# mcu.net
KiCad netlist of a schematic drawn in Altium Designer
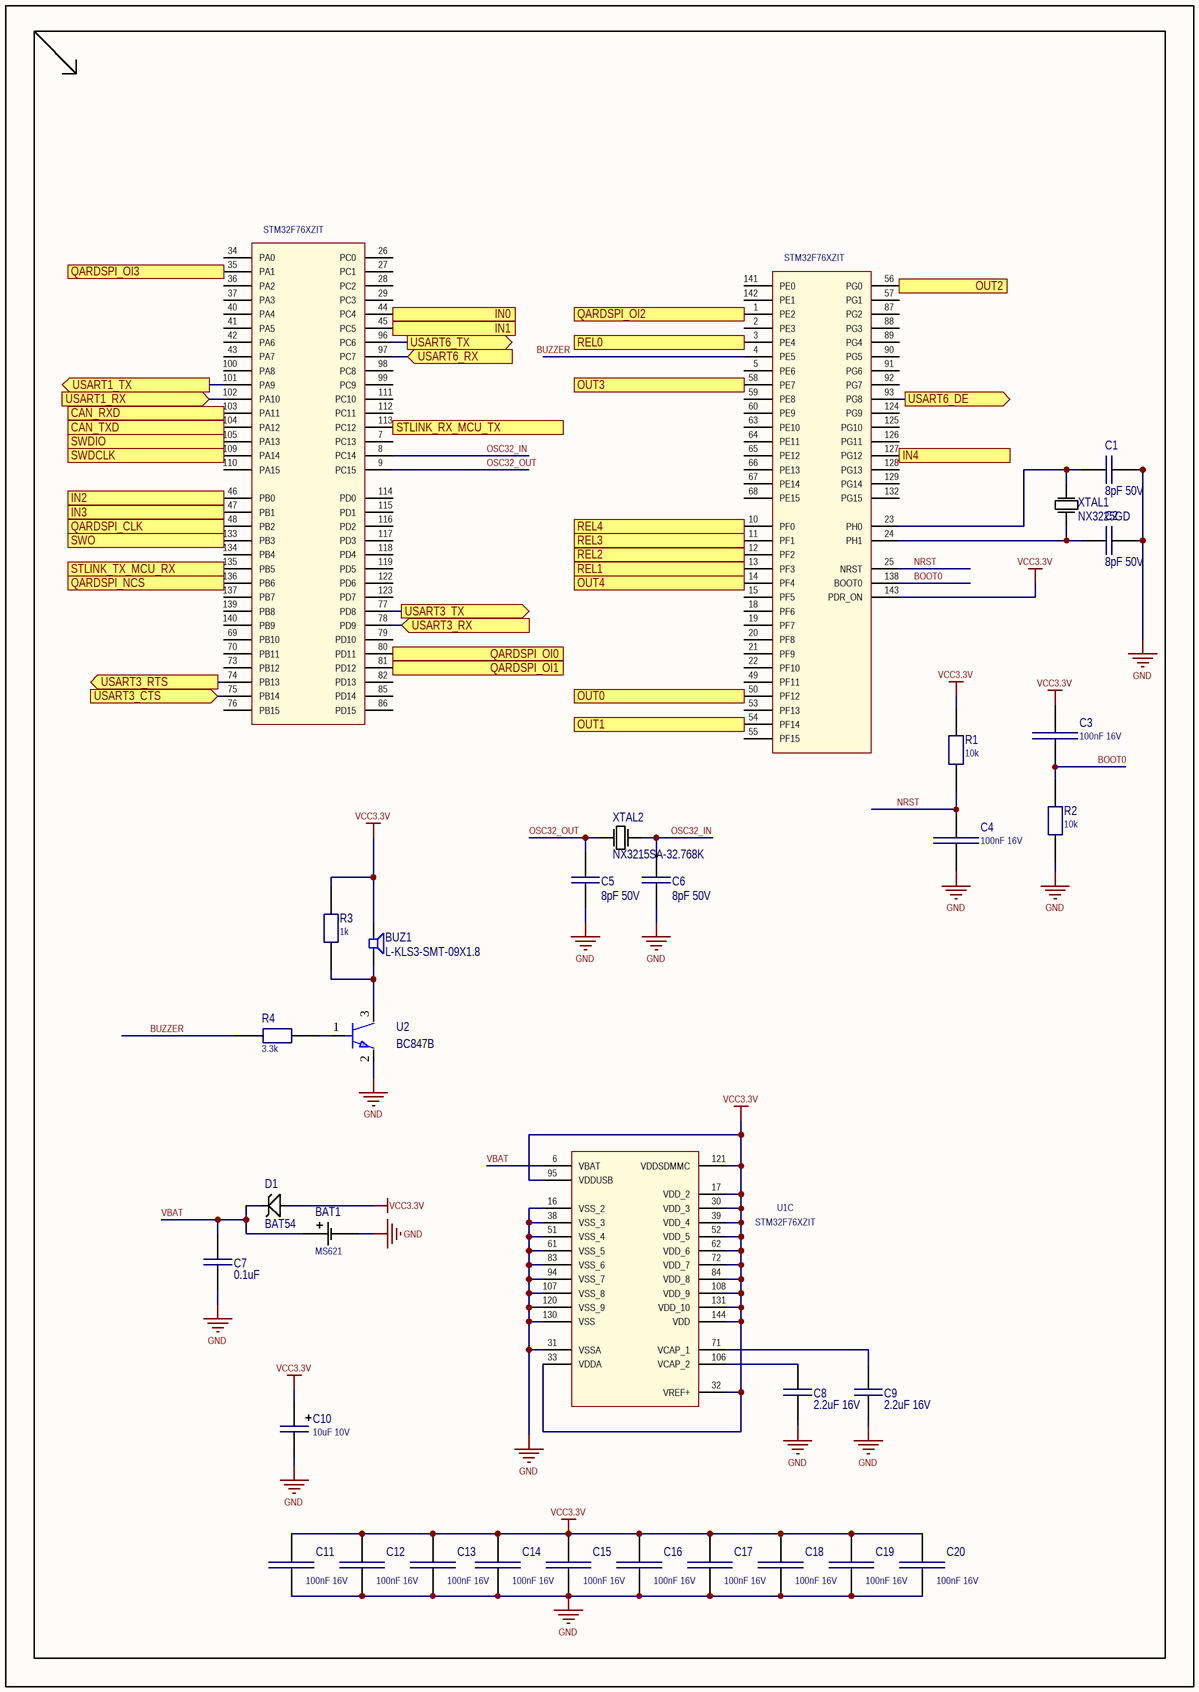
[diagram p0: mcu.schdoc]

(export (version "E")
  (design (tool "Eeschema 10.0.6"))
  (components
    (comp (ref "BAT1")
      (value "MS621")
      (footprint "battery_socets:MS621")
      (description "Battery")
      (libsource (lib "battery_socets") (part "MS621"))
    )
    (comp (ref "BUZ1")
      (value "L-KLS3-SMT-09X1.8")
      (footprint "SPKR_PKMCS0909E4000-R1")
      (description "Piezoelectric Sounders")
      (fields (field (name "ALTERNATIVE PART") "PKLCS1212E40A1-R1"))
      (libsource (lib "other") (part "BUZZER"))
    )
    (comp (ref "C1")
      (value "8pF 50V")
      (footprint "C_0603")
      (description "Capacitor")
      (fields (field (name "PART NUMBER") "CC0603DRNPO9BN8R0"))
      (libsource (lib "capacitors") (part "CAP_SMD"))
    )
    (comp (ref "C2")
      (value "8pF 50V")
      (footprint "C_0603")
      (description "Capacitor")
      (fields (field (name "PART NUMBER") "CC0603DRNPO9BN8R0"))
      (libsource (lib "capacitors") (part "CAP_SMD"))
    )
    (comp (ref "C3")
      (value "100nF 16V")
      (footprint "C_0603")
      (description "Capacitor")
      (fields (field (name "PART NUMBER") "CC0603KPX7R9BB104"))
      (libsource (lib "AX_Altium_v2.3") (part "C0603"))
    )
    (comp (ref "C4")
      (value "100nF 16V")
      (footprint "C_0603")
      (description "Capacitor")
      (fields (field (name "PART NUMBER") "CC0603KPX7R9BB104"))
      (libsource (lib "AX_Altium_v2.3") (part "C0603"))
    )
    (comp (ref "C5")
      (value "8pF 50V")
      (footprint "C_0603")
      (description "Capacitor")
      (fields (field (name "PART NUMBER") "CC0603DRNPO9BN8R0"))
      (libsource (lib "capacitors") (part "CAP_SMD"))
    )
    (comp (ref "C6")
      (value "8pF 50V")
      (footprint "C_0603")
      (description "Capacitor")
      (fields (field (name "PART NUMBER") "CC0603DRNPO9BN8R0"))
      (libsource (lib "capacitors") (part "CAP_SMD"))
    )
    (comp (ref "C7")
      (value "0.1uF")
      (footprint "C_0603")
      (description "Capacitor")
      (fields (field (name "PART NUMBER") "CC0603KPX7R9BB104"))
      (libsource (lib "capacitors") (part "CAP_SMD"))
    )
    (comp (ref "C8")
      (value "2.2uF 16V")
      (footprint "C_0603")
      (description "Capacitor")
      (fields (field (name "PART NUMBER") "CC0603KRX5R7BB225"))
      (libsource (lib "capacitors") (part "CAP_SMD"))
    )
    (comp (ref "C9")
      (value "2.2uF 16V")
      (footprint "C_0603")
      (description "Capacitor")
      (fields (field (name "PART NUMBER") "CC0603KRX5R7BB225"))
      (libsource (lib "capacitors") (part "CAP_SMD"))
    )
    (comp (ref "C10")
      (value "10uF 10V")
      (footprint "TANTAL_TYPE_A")
      (description "Tantal Capacitor")
      (fields (field (name "PART NUMBER") "293D106X9010A2TE3"))
      (libsource (lib "capacitors") (part "TANTAL_CAP"))
    )
    (comp (ref "C11")
      (value "100nF 16V")
      (footprint "C_0603")
      (description "Capacitor")
      (fields (field (name "PART NUMBER") "CC0603KPX7R9BB104"))
      (libsource (lib "AX_Altium_v2.3") (part "C0603"))
    )
    (comp (ref "C12")
      (value "100nF 16V")
      (footprint "C_0603")
      (description "Capacitor")
      (fields (field (name "PART NUMBER") "CC0603KPX7R9BB104"))
      (libsource (lib "AX_Altium_v2.3") (part "C0603"))
    )
    (comp (ref "C13")
      (value "100nF 16V")
      (footprint "C_0603")
      (description "Capacitor")
      (fields (field (name "PART NUMBER") "CC0603KPX7R9BB104"))
      (libsource (lib "AX_Altium_v2.3") (part "C0603"))
    )
    (comp (ref "C14")
      (value "100nF 16V")
      (footprint "C_0603")
      (description "Capacitor")
      (fields (field (name "PART NUMBER") "CC0603KPX7R9BB104"))
      (libsource (lib "AX_Altium_v2.3") (part "C0603"))
    )
    (comp (ref "C15")
      (value "100nF 16V")
      (footprint "C_0603")
      (description "Capacitor")
      (fields (field (name "PART NUMBER") "CC0603KPX7R9BB104"))
      (libsource (lib "AX_Altium_v2.3") (part "C0603"))
    )
    (comp (ref "C16")
      (value "100nF 16V")
      (footprint "C_0603")
      (description "Capacitor")
      (fields (field (name "PART NUMBER") "CC0603KPX7R9BB104"))
      (libsource (lib "AX_Altium_v2.3") (part "C0603"))
    )
    (comp (ref "C17")
      (value "100nF 16V")
      (footprint "C_0603")
      (description "Capacitor")
      (fields (field (name "PART NUMBER") "CC0603KPX7R9BB104"))
      (libsource (lib "AX_Altium_v2.3") (part "C0603"))
    )
    (comp (ref "C18")
      (value "100nF 16V")
      (footprint "C_0603")
      (description "Capacitor")
      (fields (field (name "PART NUMBER") "CC0603KPX7R9BB104"))
      (libsource (lib "AX_Altium_v2.3") (part "C0603"))
    )
    (comp (ref "C19")
      (value "100nF 16V")
      (footprint "C_0603")
      (description "Capacitor")
      (fields (field (name "PART NUMBER") "CC0603KPX7R9BB104"))
      (libsource (lib "AX_Altium_v2.3") (part "C0603"))
    )
    (comp (ref "C20")
      (value "100nF 16V")
      (footprint "C_0603")
      (description "Capacitor")
      (fields (field (name "PART NUMBER") "CC0603KPX7R9BB104"))
      (libsource (lib "AX_Altium_v2.3") (part "C0603"))
    )
    (comp (ref "D1")
      (value "BAT54")
      (footprint "SOT23")
      (description "Diode")
      (libsource (lib "diode") (part "BAT54"))
    )
    (comp (ref "R1")
      (value "10k")
      (footprint "R_0603")
      (description "Resistor")
      (fields (field (name "PART NUMBER") "RC0603FR-0710KL"))
      (libsource (lib "resistors") (part "RES_SMD"))
    )
    (comp (ref "R2")
      (value "10k")
      (footprint "R_0603")
      (description "Resistor")
      (fields (field (name "PART NUMBER") "RC0603FR-0710KL"))
      (libsource (lib "resistors") (part "RES_SMD"))
    )
    (comp (ref "R3")
      (value "1k")
      (footprint "R_0603")
      (description "Resistor")
      (fields (field (name "PART NUMBER") "RC0603FR-071KL"))
      (libsource (lib "resistors") (part "RES_SMD"))
    )
    (comp (ref "R4")
      (value "3.3k")
      (footprint "R_0603")
      (description "Resistor")
      (fields (field (name "PART NUMBER") "RC0603FR-073K3L"))
      (libsource (lib "resistors") (part "RES_SMD"))
    )
    (comp (ref "U1")
      (value "STM32F76XZIT")
      (footprint "TQFP144_M")
      (description "MCU")
      (fields
        (field (name "MANUFACTURER_PART_NUMBER") "STM32F76XZXT")
        (field (name "PART NUMBER") "STM32F765ZGT")
        (field (name "COPYRIGHT") "Copyright (C) 2016 Accelerated Designs. All rights reserved")
      )
      (libsource (lib "STM32 F4") (part "STM32F76XZXT"))
    )
    (comp (ref "U2")
      (value "BC847B")
      (footprint "SOT23")
      (description "Transistor")
      (libsource (lib "AX_Altium_v2.3") (part "BC847B"))
    )
    (comp (ref "XTAL1")
      (value "NX3225GD")
      (footprint "NX3225GD")
      (description "Crystal Oscillator")
      (fields (field (name "PART NUMBER") "NX3225GD-8MHZ-EXS00A-CG05041"))
      (libsource (lib "crystals_oscillators") (part "NX3225GD"))
    )
    (comp (ref "XTAL2")
      (value "NX3215SA-32.768K")
      (footprint "XTAL_NX3215SA-32.768K-STD-MUA-8")
      (description "Crystal Oscillator")
      (fields (field (name "PART NUMBER") "NX3215SA-32.768K-10PPM-45KOHM-6PF"))
      (libsource (lib "crystals_oscillators") (part "NX3215SA-32.768K"))
    )
  )
  (nets
    (net (code "1") (name "/BOOT0") (class "Default")
      (node (ref "C3") (pin "2") (pinfunction "2_2") (pintype "passive"))
      (node (ref "R2") (pin "2") (pinfunction "2_2") (pintype "passive"))
      (node (ref "U1") (pin "138") (pinfunction "BOOT0_138") (pintype "passive"))
    )
    (net (code "2") (name "/BUZZER") (class "Default")
      (node (ref "R4") (pin "1") (pinfunction "1_1") (pintype "passive"))
      (node (ref "U1") (pin "4") (pinfunction "PE5_4") (pintype "passive"))
    )
    (net (code "3") (name "/CAN_RXD") (class "Default")
      (node (ref "U1") (pin "103") (pinfunction "PA11_103") (pintype "passive"))
    )
    (net (code "4") (name "/CAN_TXD") (class "Default")
      (node (ref "U1") (pin "104") (pinfunction "PA12_104") (pintype "passive"))
    )
    (net (code "5") (name "/IN0") (class "Default")
      (node (ref "U1") (pin "44") (pinfunction "PC4_44") (pintype "passive"))
    )
    (net (code "6") (name "/IN1") (class "Default")
      (node (ref "U1") (pin "45") (pinfunction "PC5_45") (pintype "passive"))
    )
    (net (code "7") (name "/IN2") (class "Default")
      (node (ref "U1") (pin "46") (pinfunction "PB0_46") (pintype "passive"))
    )
    (net (code "8") (name "/IN3") (class "Default")
      (node (ref "U1") (pin "47") (pinfunction "PB1_47") (pintype "passive"))
    )
    (net (code "9") (name "/IN4") (class "Default")
      (node (ref "U1") (pin "127") (pinfunction "PG12_127") (pintype "passive"))
    )
    (net (code "10") (name "/NRST") (class "Default")
      (node (ref "C4") (pin "2") (pinfunction "2_2") (pintype "passive"))
      (node (ref "R1") (pin "1") (pinfunction "1_1") (pintype "passive"))
      (node (ref "U1") (pin "25") (pinfunction "NRST_25") (pintype "passive"))
    )
    (net (code "11") (name "/OSC32_IN") (class "Default")
      (node (ref "C6") (pin "2") (pinfunction "2_2") (pintype "passive"))
      (node (ref "U1") (pin "8") (pinfunction "PC14_8") (pintype "passive"))
      (node (ref "XTAL2") (pin "2") (pinfunction "OSC2_2") (pintype "passive"))
    )
    (net (code "12") (name "/OSC32_OUT") (class "Default")
      (node (ref "C5") (pin "2") (pinfunction "2_2") (pintype "passive"))
      (node (ref "U1") (pin "9") (pinfunction "PC15_9") (pintype "passive"))
      (node (ref "XTAL2") (pin "1") (pinfunction "OSC1_1") (pintype "passive"))
    )
    (net (code "13") (name "/OUT0") (class "Default")
      (node (ref "U1") (pin "50") (pinfunction "PF12_50") (pintype "passive"))
    )
    (net (code "14") (name "/OUT1") (class "Default")
      (node (ref "U1") (pin "54") (pinfunction "PF14_54") (pintype "passive"))
    )
    (net (code "15") (name "/OUT2") (class "Default")
      (node (ref "U1") (pin "56") (pinfunction "PG0_56") (pintype "passive"))
    )
    (net (code "16") (name "/OUT3") (class "Default")
      (node (ref "U1") (pin "58") (pinfunction "PE7_58") (pintype "passive"))
    )
    (net (code "17") (name "/OUT4") (class "Default")
      (node (ref "U1") (pin "14") (pinfunction "PF4_14") (pintype "passive"))
    )
    (net (code "18") (name "/QARDSPI_CLK") (class "Default")
      (node (ref "U1") (pin "48") (pinfunction "PB2_48") (pintype "passive"))
    )
    (net (code "19") (name "/QARDSPI_NCS") (class "Default")
      (node (ref "U1") (pin "136") (pinfunction "PB6_136") (pintype "passive"))
    )
    (net (code "20") (name "/QARDSPI_OI0") (class "Default")
      (node (ref "U1") (pin "80") (pinfunction "PD11_80") (pintype "passive"))
    )
    (net (code "21") (name "/QARDSPI_OI1") (class "Default")
      (node (ref "U1") (pin "81") (pinfunction "PD12_81") (pintype "passive"))
    )
    (net (code "22") (name "/QARDSPI_OI2") (class "Default")
      (node (ref "U1") (pin "1") (pinfunction "PE2_1") (pintype "passive"))
    )
    (net (code "23") (name "/QARDSPI_OI3") (class "Default")
      (node (ref "U1") (pin "35") (pinfunction "PA1_35") (pintype "passive"))
    )
    (net (code "24") (name "/REL0") (class "Default")
      (node (ref "U1") (pin "3") (pinfunction "PE4_3") (pintype "passive"))
    )
    (net (code "25") (name "/REL1") (class "Default")
      (node (ref "U1") (pin "13") (pinfunction "PF3_13") (pintype "passive"))
    )
    (net (code "26") (name "/REL2") (class "Default")
      (node (ref "U1") (pin "12") (pinfunction "PF2_12") (pintype "passive"))
    )
    (net (code "27") (name "/REL3") (class "Default")
      (node (ref "U1") (pin "11") (pinfunction "PF1_11") (pintype "passive"))
    )
    (net (code "28") (name "/REL4") (class "Default")
      (node (ref "U1") (pin "10") (pinfunction "PF0_10") (pintype "passive"))
    )
    (net (code "29") (name "/STLINK_RX_MCU_TX") (class "Default")
      (node (ref "U1") (pin "113") (pinfunction "PC12_113") (pintype "passive"))
    )
    (net (code "30") (name "/STLINK_TX_MCU_RX") (class "Default")
      (node (ref "U1") (pin "135") (pinfunction "PB5_135") (pintype "passive"))
    )
    (net (code "31") (name "/SWDCLK") (class "Default")
      (node (ref "U1") (pin "109") (pinfunction "PA14_109") (pintype "passive"))
    )
    (net (code "32") (name "/SWDIO") (class "Default")
      (node (ref "U1") (pin "105") (pinfunction "PA13_105") (pintype "passive"))
    )
    (net (code "33") (name "/SWO") (class "Default")
      (node (ref "U1") (pin "133") (pinfunction "PB3_133") (pintype "passive"))
    )
    (net (code "34") (name "/USART1_RX") (class "Default")
      (node (ref "U1") (pin "102") (pinfunction "PA10_102") (pintype "passive"))
    )
    (net (code "35") (name "/USART1_TX") (class "Default")
      (node (ref "U1") (pin "101") (pinfunction "PA9_101") (pintype "passive"))
    )
    (net (code "36") (name "/USART3_CTS") (class "Default")
      (node (ref "U1") (pin "75") (pinfunction "PB14_75") (pintype "passive"))
    )
    (net (code "37") (name "/USART3_RTS") (class "Default")
      (node (ref "U1") (pin "74") (pinfunction "PB13_74") (pintype "passive"))
    )
    (net (code "38") (name "/USART3_RX") (class "Default")
      (node (ref "U1") (pin "78") (pinfunction "PD9_78") (pintype "passive"))
    )
    (net (code "39") (name "/USART3_TX") (class "Default")
      (node (ref "U1") (pin "77") (pinfunction "PD8_77") (pintype "passive"))
    )
    (net (code "40") (name "/USART6_DE") (class "Default")
      (node (ref "U1") (pin "93") (pinfunction "PG8_93") (pintype "passive"))
    )
    (net (code "41") (name "/USART6_RX") (class "Default")
      (node (ref "U1") (pin "97") (pinfunction "PC7_97") (pintype "passive"))
    )
    (net (code "42") (name "/USART6_TX") (class "Default")
      (node (ref "U1") (pin "96") (pinfunction "PC6_96") (pintype "passive"))
    )
    (net (code "43") (name "/VBAT") (class "Default")
      (node (ref "BAT1") (pin "1") (pinfunction "+_1") (pintype "passive"))
      (node (ref "C7") (pin "2") (pinfunction "2_2") (pintype "passive"))
      (node (ref "D1") (pin "3") (pinfunction "3_3") (pintype "passive"))
      (node (ref "U1") (pin "6") (pinfunction "VBAT_6") (pintype "passive"))
    )
    (net (code "44") (name "GND") (class "Default")
      (node (ref "BAT1") (pin "0") (pinfunction "-_0") (pintype "passive"))
      (node (ref "C1") (pin "1") (pinfunction "1_1") (pintype "passive"))
      (node (ref "C10") (pin "2") (pinfunction "2_2") (pintype "passive"))
      (node (ref "C11") (pin "1") (pinfunction "1_1") (pintype "passive"))
      (node (ref "C12") (pin "1") (pinfunction "1_1") (pintype "passive"))
      (node (ref "C13") (pin "1") (pinfunction "1_1") (pintype "passive"))
      (node (ref "C14") (pin "1") (pinfunction "1_1") (pintype "passive"))
      (node (ref "C15") (pin "1") (pinfunction "1_1") (pintype "passive"))
      (node (ref "C16") (pin "1") (pinfunction "1_1") (pintype "passive"))
      (node (ref "C17") (pin "1") (pinfunction "1_1") (pintype "passive"))
      (node (ref "C18") (pin "1") (pinfunction "1_1") (pintype "passive"))
      (node (ref "C19") (pin "1") (pinfunction "1_1") (pintype "passive"))
      (node (ref "C2") (pin "1") (pinfunction "1_1") (pintype "passive"))
      (node (ref "C20") (pin "1") (pinfunction "1_1") (pintype "passive"))
      (node (ref "C4") (pin "1") (pinfunction "1_1") (pintype "passive"))
      (node (ref "C5") (pin "1") (pinfunction "1_1") (pintype "passive"))
      (node (ref "C6") (pin "1") (pinfunction "1_1") (pintype "passive"))
      (node (ref "C7") (pin "1") (pinfunction "1_1") (pintype "passive"))
      (node (ref "C8") (pin "1") (pinfunction "1_1") (pintype "passive"))
      (node (ref "C9") (pin "1") (pinfunction "1_1") (pintype "passive"))
      (node (ref "R2") (pin "1") (pinfunction "1_1") (pintype "passive"))
      (node (ref "U1") (pin "107") (pinfunction "VSS_8_107") (pintype "passive"))
      (node (ref "U1") (pin "120") (pinfunction "VSS_9_120") (pintype "passive"))
      (node (ref "U1") (pin "130") (pinfunction "VSS_130") (pintype "passive"))
      (node (ref "U1") (pin "16") (pinfunction "VSS_2_16") (pintype "passive"))
      (node (ref "U1") (pin "31") (pinfunction "VSSA_31") (pintype "passive"))
      (node (ref "U1") (pin "38") (pinfunction "VSS_3_38") (pintype "passive"))
      (node (ref "U1") (pin "51") (pinfunction "VSS_4_51") (pintype "passive"))
      (node (ref "U1") (pin "61") (pinfunction "VSS_5_61") (pintype "passive"))
      (node (ref "U1") (pin "83") (pinfunction "VSS_6_83") (pintype "passive"))
      (node (ref "U1") (pin "94") (pinfunction "VSS_7_94") (pintype "passive"))
      (node (ref "U2") (pin "2") (pintype "passive"))
    )
    (net (code "45") (name "Net-(BUZ1-Pad2)") (class "Default")
      (node (ref "BUZ1") (pin "2") (pinfunction "2_2") (pintype "passive"))
      (node (ref "R3") (pin "1") (pinfunction "1_1") (pintype "passive"))
      (node (ref "U2") (pin "3") (pintype "passive"))
    )
    (net (code "46") (name "Net-(R4-Pad2)") (class "Default")
      (node (ref "R4") (pin "2") (pinfunction "2_2") (pintype "passive"))
      (node (ref "U2") (pin "1") (pintype "passive"))
    )
    (net (code "47") (name "Net-(U1B-PH0)") (class "Default")
      (node (ref "C1") (pin "2") (pinfunction "2_2") (pintype "passive"))
      (node (ref "U1") (pin "23") (pinfunction "PH0_23") (pintype "passive"))
      (node (ref "XTAL1") (pin "2") (pinfunction "OSC2_2") (pintype "passive"))
    )
    (net (code "48") (name "Net-(U1B-PH1)") (class "Default")
      (node (ref "C2") (pin "2") (pinfunction "2_2") (pintype "passive"))
      (node (ref "U1") (pin "24") (pinfunction "PH1_24") (pintype "passive"))
      (node (ref "XTAL1") (pin "1") (pinfunction "OSC1_1") (pintype "passive"))
    )
    (net (code "49") (name "Net-(U1C-VCAP_1)") (class "Default")
      (node (ref "C9") (pin "2") (pinfunction "2_2") (pintype "passive"))
      (node (ref "U1") (pin "71") (pinfunction "VCAP_1_71") (pintype "passive"))
    )
    (net (code "50") (name "Net-(U1C-VCAP_2)") (class "Default")
      (node (ref "C8") (pin "2") (pinfunction "2_2") (pintype "passive"))
      (node (ref "U1") (pin "106") (pinfunction "VCAP_2_106") (pintype "passive"))
    )
    (net (code "51") (name "VCC3.3V") (class "Default")
      (node (ref "BUZ1") (pin "1") (pinfunction "1_1") (pintype "passive"))
      (node (ref "C10") (pin "1") (pinfunction "1_1") (pintype "passive"))
      (node (ref "C11") (pin "2") (pinfunction "2_2") (pintype "passive"))
      (node (ref "C12") (pin "2") (pinfunction "2_2") (pintype "passive"))
      (node (ref "C13") (pin "2") (pinfunction "2_2") (pintype "passive"))
      (node (ref "C14") (pin "2") (pinfunction "2_2") (pintype "passive"))
      (node (ref "C15") (pin "2") (pinfunction "2_2") (pintype "passive"))
      (node (ref "C16") (pin "2") (pinfunction "2_2") (pintype "passive"))
      (node (ref "C17") (pin "2") (pinfunction "2_2") (pintype "passive"))
      (node (ref "C18") (pin "2") (pinfunction "2_2") (pintype "passive"))
      (node (ref "C19") (pin "2") (pinfunction "2_2") (pintype "passive"))
      (node (ref "C20") (pin "2") (pinfunction "2_2") (pintype "passive"))
      (node (ref "C3") (pin "1") (pinfunction "1_1") (pintype "passive"))
      (node (ref "D1") (pin "1") (pinfunction "1_1") (pintype "passive"))
      (node (ref "R1") (pin "2") (pinfunction "2_2") (pintype "passive"))
      (node (ref "R3") (pin "2") (pinfunction "2_2") (pintype "passive"))
      (node (ref "U1") (pin "108") (pinfunction "VDD_9_108") (pintype "passive"))
      (node (ref "U1") (pin "121") (pinfunction "VDDSDMMC_121") (pintype "passive"))
      (node (ref "U1") (pin "131") (pinfunction "VDD_10_131") (pintype "passive"))
      (node (ref "U1") (pin "143") (pinfunction "PDR_ON_143") (pintype "passive"))
      (node (ref "U1") (pin "144") (pinfunction "VDD_144") (pintype "passive"))
      (node (ref "U1") (pin "17") (pinfunction "VDD_2_17") (pintype "passive"))
      (node (ref "U1") (pin "30") (pinfunction "VDD_3_30") (pintype "passive"))
      (node (ref "U1") (pin "32") (pinfunction "VREF+_32") (pintype "passive"))
      (node (ref "U1") (pin "33") (pinfunction "VDDA_33") (pintype "passive"))
      (node (ref "U1") (pin "39") (pinfunction "VDD_4_39") (pintype "passive"))
      (node (ref "U1") (pin "52") (pinfunction "VDD_5_52") (pintype "passive"))
      (node (ref "U1") (pin "62") (pinfunction "VDD_6_62") (pintype "passive"))
      (node (ref "U1") (pin "72") (pinfunction "VDD_7_72") (pintype "passive"))
      (node (ref "U1") (pin "84") (pinfunction "VDD_8_84") (pintype "passive"))
      (node (ref "U1") (pin "95") (pinfunction "VDDUSB_95") (pintype "passive"))
    )
    (net (code "52") (name "unconnected-(U1A-PA0-Pad34)") (class "Default")
      (node (ref "U1") (pin "34") (pinfunction "PA0_34") (pintype "passive"))
    )
    (net (code "53") (name "unconnected-(U1A-PA2-Pad36)") (class "Default")
      (node (ref "U1") (pin "36") (pinfunction "PA2_36") (pintype "passive"))
    )
    (net (code "54") (name "unconnected-(U1A-PA3-Pad37)") (class "Default")
      (node (ref "U1") (pin "37") (pinfunction "PA3_37") (pintype "passive"))
    )
    (net (code "55") (name "unconnected-(U1A-PA4-Pad40)") (class "Default")
      (node (ref "U1") (pin "40") (pinfunction "PA4_40") (pintype "passive"))
    )
    (net (code "56") (name "unconnected-(U1A-PA5-Pad41)") (class "Default")
      (node (ref "U1") (pin "41") (pinfunction "PA5_41") (pintype "passive"))
    )
    (net (code "57") (name "unconnected-(U1A-PA6-Pad42)") (class "Default")
      (node (ref "U1") (pin "42") (pinfunction "PA6_42") (pintype "passive"))
    )
    (net (code "58") (name "unconnected-(U1A-PA7-Pad43)") (class "Default")
      (node (ref "U1") (pin "43") (pinfunction "PA7_43") (pintype "passive"))
    )
    (net (code "59") (name "unconnected-(U1A-PA8-Pad100)") (class "Default")
      (node (ref "U1") (pin "100") (pinfunction "PA8_100") (pintype "passive"))
    )
    (net (code "60") (name "unconnected-(U1A-PA15-Pad110)") (class "Default")
      (node (ref "U1") (pin "110") (pinfunction "PA15_110") (pintype "passive"))
    )
    (net (code "61") (name "unconnected-(U1A-PB4-Pad134)") (class "Default")
      (node (ref "U1") (pin "134") (pinfunction "PB4_134") (pintype "passive"))
    )
    (net (code "62") (name "unconnected-(U1A-PB7-Pad137)") (class "Default")
      (node (ref "U1") (pin "137") (pinfunction "PB7_137") (pintype "passive"))
    )
    (net (code "63") (name "unconnected-(U1A-PB8-Pad139)") (class "Default")
      (node (ref "U1") (pin "139") (pinfunction "PB8_139") (pintype "passive"))
    )
    (net (code "64") (name "unconnected-(U1A-PB9-Pad140)") (class "Default")
      (node (ref "U1") (pin "140") (pinfunction "PB9_140") (pintype "passive"))
    )
    (net (code "65") (name "unconnected-(U1A-PB10-Pad69)") (class "Default")
      (node (ref "U1") (pin "69") (pinfunction "PB10_69") (pintype "passive"))
    )
    (net (code "66") (name "unconnected-(U1A-PB11-Pad70)") (class "Default")
      (node (ref "U1") (pin "70") (pinfunction "PB11_70") (pintype "passive"))
    )
    (net (code "67") (name "unconnected-(U1A-PB12-Pad73)") (class "Default")
      (node (ref "U1") (pin "73") (pinfunction "PB12_73") (pintype "passive"))
    )
    (net (code "68") (name "unconnected-(U1A-PB15-Pad76)") (class "Default")
      (node (ref "U1") (pin "76") (pinfunction "PB15_76") (pintype "passive"))
    )
    (net (code "69") (name "unconnected-(U1A-PC0-Pad26)") (class "Default")
      (node (ref "U1") (pin "26") (pinfunction "PC0_26") (pintype "passive"))
    )
    (net (code "70") (name "unconnected-(U1A-PC1-Pad27)") (class "Default")
      (node (ref "U1") (pin "27") (pinfunction "PC1_27") (pintype "passive"))
    )
    (net (code "71") (name "unconnected-(U1A-PC2-Pad28)") (class "Default")
      (node (ref "U1") (pin "28") (pinfunction "PC2_28") (pintype "passive"))
    )
    (net (code "72") (name "unconnected-(U1A-PC3-Pad29)") (class "Default")
      (node (ref "U1") (pin "29") (pinfunction "PC3_29") (pintype "passive"))
    )
    (net (code "73") (name "unconnected-(U1A-PC8-Pad98)") (class "Default")
      (node (ref "U1") (pin "98") (pinfunction "PC8_98") (pintype "passive"))
    )
    (net (code "74") (name "unconnected-(U1A-PC9-Pad99)") (class "Default")
      (node (ref "U1") (pin "99") (pinfunction "PC9_99") (pintype "passive"))
    )
    (net (code "75") (name "unconnected-(U1A-PC10-Pad111)") (class "Default")
      (node (ref "U1") (pin "111") (pinfunction "PC10_111") (pintype "passive"))
    )
    (net (code "76") (name "unconnected-(U1A-PC11-Pad112)") (class "Default")
      (node (ref "U1") (pin "112") (pinfunction "PC11_112") (pintype "passive"))
    )
    (net (code "77") (name "unconnected-(U1A-PC13-Pad7)") (class "Default")
      (node (ref "U1") (pin "7") (pinfunction "PC13_7") (pintype "passive"))
    )
    (net (code "78") (name "unconnected-(U1A-PD0-Pad114)") (class "Default")
      (node (ref "U1") (pin "114") (pinfunction "PD0_114") (pintype "passive"))
    )
    (net (code "79") (name "unconnected-(U1A-PD1-Pad115)") (class "Default")
      (node (ref "U1") (pin "115") (pinfunction "PD1_115") (pintype "passive"))
    )
    (net (code "80") (name "unconnected-(U1A-PD2-Pad116)") (class "Default")
      (node (ref "U1") (pin "116") (pinfunction "PD2_116") (pintype "passive"))
    )
    (net (code "81") (name "unconnected-(U1A-PD3-Pad117)") (class "Default")
      (node (ref "U1") (pin "117") (pinfunction "PD3_117") (pintype "passive"))
    )
    (net (code "82") (name "unconnected-(U1A-PD4-Pad118)") (class "Default")
      (node (ref "U1") (pin "118") (pinfunction "PD4_118") (pintype "passive"))
    )
    (net (code "83") (name "unconnected-(U1A-PD5-Pad119)") (class "Default")
      (node (ref "U1") (pin "119") (pinfunction "PD5_119") (pintype "passive"))
    )
    (net (code "84") (name "unconnected-(U1A-PD6-Pad122)") (class "Default")
      (node (ref "U1") (pin "122") (pinfunction "PD6_122") (pintype "passive"))
    )
    (net (code "85") (name "unconnected-(U1A-PD7-Pad123)") (class "Default")
      (node (ref "U1") (pin "123") (pinfunction "PD7_123") (pintype "passive"))
    )
    (net (code "86") (name "unconnected-(U1A-PD10-Pad79)") (class "Default")
      (node (ref "U1") (pin "79") (pinfunction "PD10_79") (pintype "passive"))
    )
    (net (code "87") (name "unconnected-(U1A-PD13-Pad82)") (class "Default")
      (node (ref "U1") (pin "82") (pinfunction "PD13_82") (pintype "passive"))
    )
    (net (code "88") (name "unconnected-(U1A-PD14-Pad85)") (class "Default")
      (node (ref "U1") (pin "85") (pinfunction "PD14_85") (pintype "passive"))
    )
    (net (code "89") (name "unconnected-(U1A-PD15-Pad86)") (class "Default")
      (node (ref "U1") (pin "86") (pinfunction "PD15_86") (pintype "passive"))
    )
    (net (code "90") (name "unconnected-(U1B-PE0-Pad141)") (class "Default")
      (node (ref "U1") (pin "141") (pinfunction "PE0_141") (pintype "passive"))
    )
    (net (code "91") (name "unconnected-(U1B-PE1-Pad142)") (class "Default")
      (node (ref "U1") (pin "142") (pinfunction "PE1_142") (pintype "passive"))
    )
    (net (code "92") (name "unconnected-(U1B-PE3-Pad2)") (class "Default")
      (node (ref "U1") (pin "2") (pinfunction "PE3_2") (pintype "passive"))
    )
    (net (code "93") (name "unconnected-(U1B-PE6-Pad5)") (class "Default")
      (node (ref "U1") (pin "5") (pinfunction "PE6_5") (pintype "passive"))
    )
    (net (code "94") (name "unconnected-(U1B-PE8-Pad59)") (class "Default")
      (node (ref "U1") (pin "59") (pinfunction "PE8_59") (pintype "passive"))
    )
    (net (code "95") (name "unconnected-(U1B-PE9-Pad60)") (class "Default")
      (node (ref "U1") (pin "60") (pinfunction "PE9_60") (pintype "passive"))
    )
    (net (code "96") (name "unconnected-(U1B-PE10-Pad63)") (class "Default")
      (node (ref "U1") (pin "63") (pinfunction "PE10_63") (pintype "passive"))
    )
    (net (code "97") (name "unconnected-(U1B-PE11-Pad64)") (class "Default")
      (node (ref "U1") (pin "64") (pinfunction "PE11_64") (pintype "passive"))
    )
    (net (code "98") (name "unconnected-(U1B-PE12-Pad65)") (class "Default")
      (node (ref "U1") (pin "65") (pinfunction "PE12_65") (pintype "passive"))
    )
    (net (code "99") (name "unconnected-(U1B-PE13-Pad66)") (class "Default")
      (node (ref "U1") (pin "66") (pinfunction "PE13_66") (pintype "passive"))
    )
    (net (code "100") (name "unconnected-(U1B-PE14-Pad67)") (class "Default")
      (node (ref "U1") (pin "67") (pinfunction "PE14_67") (pintype "passive"))
    )
    (net (code "101") (name "unconnected-(U1B-PE15-Pad68)") (class "Default")
      (node (ref "U1") (pin "68") (pinfunction "PE15_68") (pintype "passive"))
    )
    (net (code "102") (name "unconnected-(U1B-PF5-Pad15)") (class "Default")
      (node (ref "U1") (pin "15") (pinfunction "PF5_15") (pintype "passive"))
    )
    (net (code "103") (name "unconnected-(U1B-PF6-Pad18)") (class "Default")
      (node (ref "U1") (pin "18") (pinfunction "PF6_18") (pintype "passive"))
    )
    (net (code "104") (name "unconnected-(U1B-PF7-Pad19)") (class "Default")
      (node (ref "U1") (pin "19") (pinfunction "PF7_19") (pintype "passive"))
    )
    (net (code "105") (name "unconnected-(U1B-PF8-Pad20)") (class "Default")
      (node (ref "U1") (pin "20") (pinfunction "PF8_20") (pintype "passive"))
    )
    (net (code "106") (name "unconnected-(U1B-PF9-Pad21)") (class "Default")
      (node (ref "U1") (pin "21") (pinfunction "PF9_21") (pintype "passive"))
    )
    (net (code "107") (name "unconnected-(U1B-PF10-Pad22)") (class "Default")
      (node (ref "U1") (pin "22") (pinfunction "PF10_22") (pintype "passive"))
    )
    (net (code "108") (name "unconnected-(U1B-PF11-Pad49)") (class "Default")
      (node (ref "U1") (pin "49") (pinfunction "PF11_49") (pintype "passive"))
    )
    (net (code "109") (name "unconnected-(U1B-PF13-Pad53)") (class "Default")
      (node (ref "U1") (pin "53") (pinfunction "PF13_53") (pintype "passive"))
    )
    (net (code "110") (name "unconnected-(U1B-PF15-Pad55)") (class "Default")
      (node (ref "U1") (pin "55") (pinfunction "PF15_55") (pintype "passive"))
    )
    (net (code "111") (name "unconnected-(U1B-PG1-Pad57)") (class "Default")
      (node (ref "U1") (pin "57") (pinfunction "PG1_57") (pintype "passive"))
    )
    (net (code "112") (name "unconnected-(U1B-PG2-Pad87)") (class "Default")
      (node (ref "U1") (pin "87") (pinfunction "PG2_87") (pintype "passive"))
    )
    (net (code "113") (name "unconnected-(U1B-PG3-Pad88)") (class "Default")
      (node (ref "U1") (pin "88") (pinfunction "PG3_88") (pintype "passive"))
    )
    (net (code "114") (name "unconnected-(U1B-PG4-Pad89)") (class "Default")
      (node (ref "U1") (pin "89") (pinfunction "PG4_89") (pintype "passive"))
    )
    (net (code "115") (name "unconnected-(U1B-PG5-Pad90)") (class "Default")
      (node (ref "U1") (pin "90") (pinfunction "PG5_90") (pintype "passive"))
    )
    (net (code "116") (name "unconnected-(U1B-PG6-Pad91)") (class "Default")
      (node (ref "U1") (pin "91") (pinfunction "PG6_91") (pintype "passive"))
    )
    (net (code "117") (name "unconnected-(U1B-PG7-Pad92)") (class "Default")
      (node (ref "U1") (pin "92") (pinfunction "PG7_92") (pintype "passive"))
    )
    (net (code "118") (name "unconnected-(U1B-PG9-Pad124)") (class "Default")
      (node (ref "U1") (pin "124") (pinfunction "PG9_124") (pintype "passive"))
    )
    (net (code "119") (name "unconnected-(U1B-PG10-Pad125)") (class "Default")
      (node (ref "U1") (pin "125") (pinfunction "PG10_125") (pintype "passive"))
    )
    (net (code "120") (name "unconnected-(U1B-PG11-Pad126)") (class "Default")
      (node (ref "U1") (pin "126") (pinfunction "PG11_126") (pintype "passive"))
    )
    (net (code "121") (name "unconnected-(U1B-PG13-Pad128)") (class "Default")
      (node (ref "U1") (pin "128") (pinfunction "PG13_128") (pintype "passive"))
    )
    (net (code "122") (name "unconnected-(U1B-PG14-Pad129)") (class "Default")
      (node (ref "U1") (pin "129") (pinfunction "PG14_129") (pintype "passive"))
    )
    (net (code "123") (name "unconnected-(U1B-PG15-Pad132)") (class "Default")
      (node (ref "U1") (pin "132") (pinfunction "PG15_132") (pintype "passive"))
    )
  )
)
